# ADC.net
KiCad netlist of a schematic drawn in Altium Designer
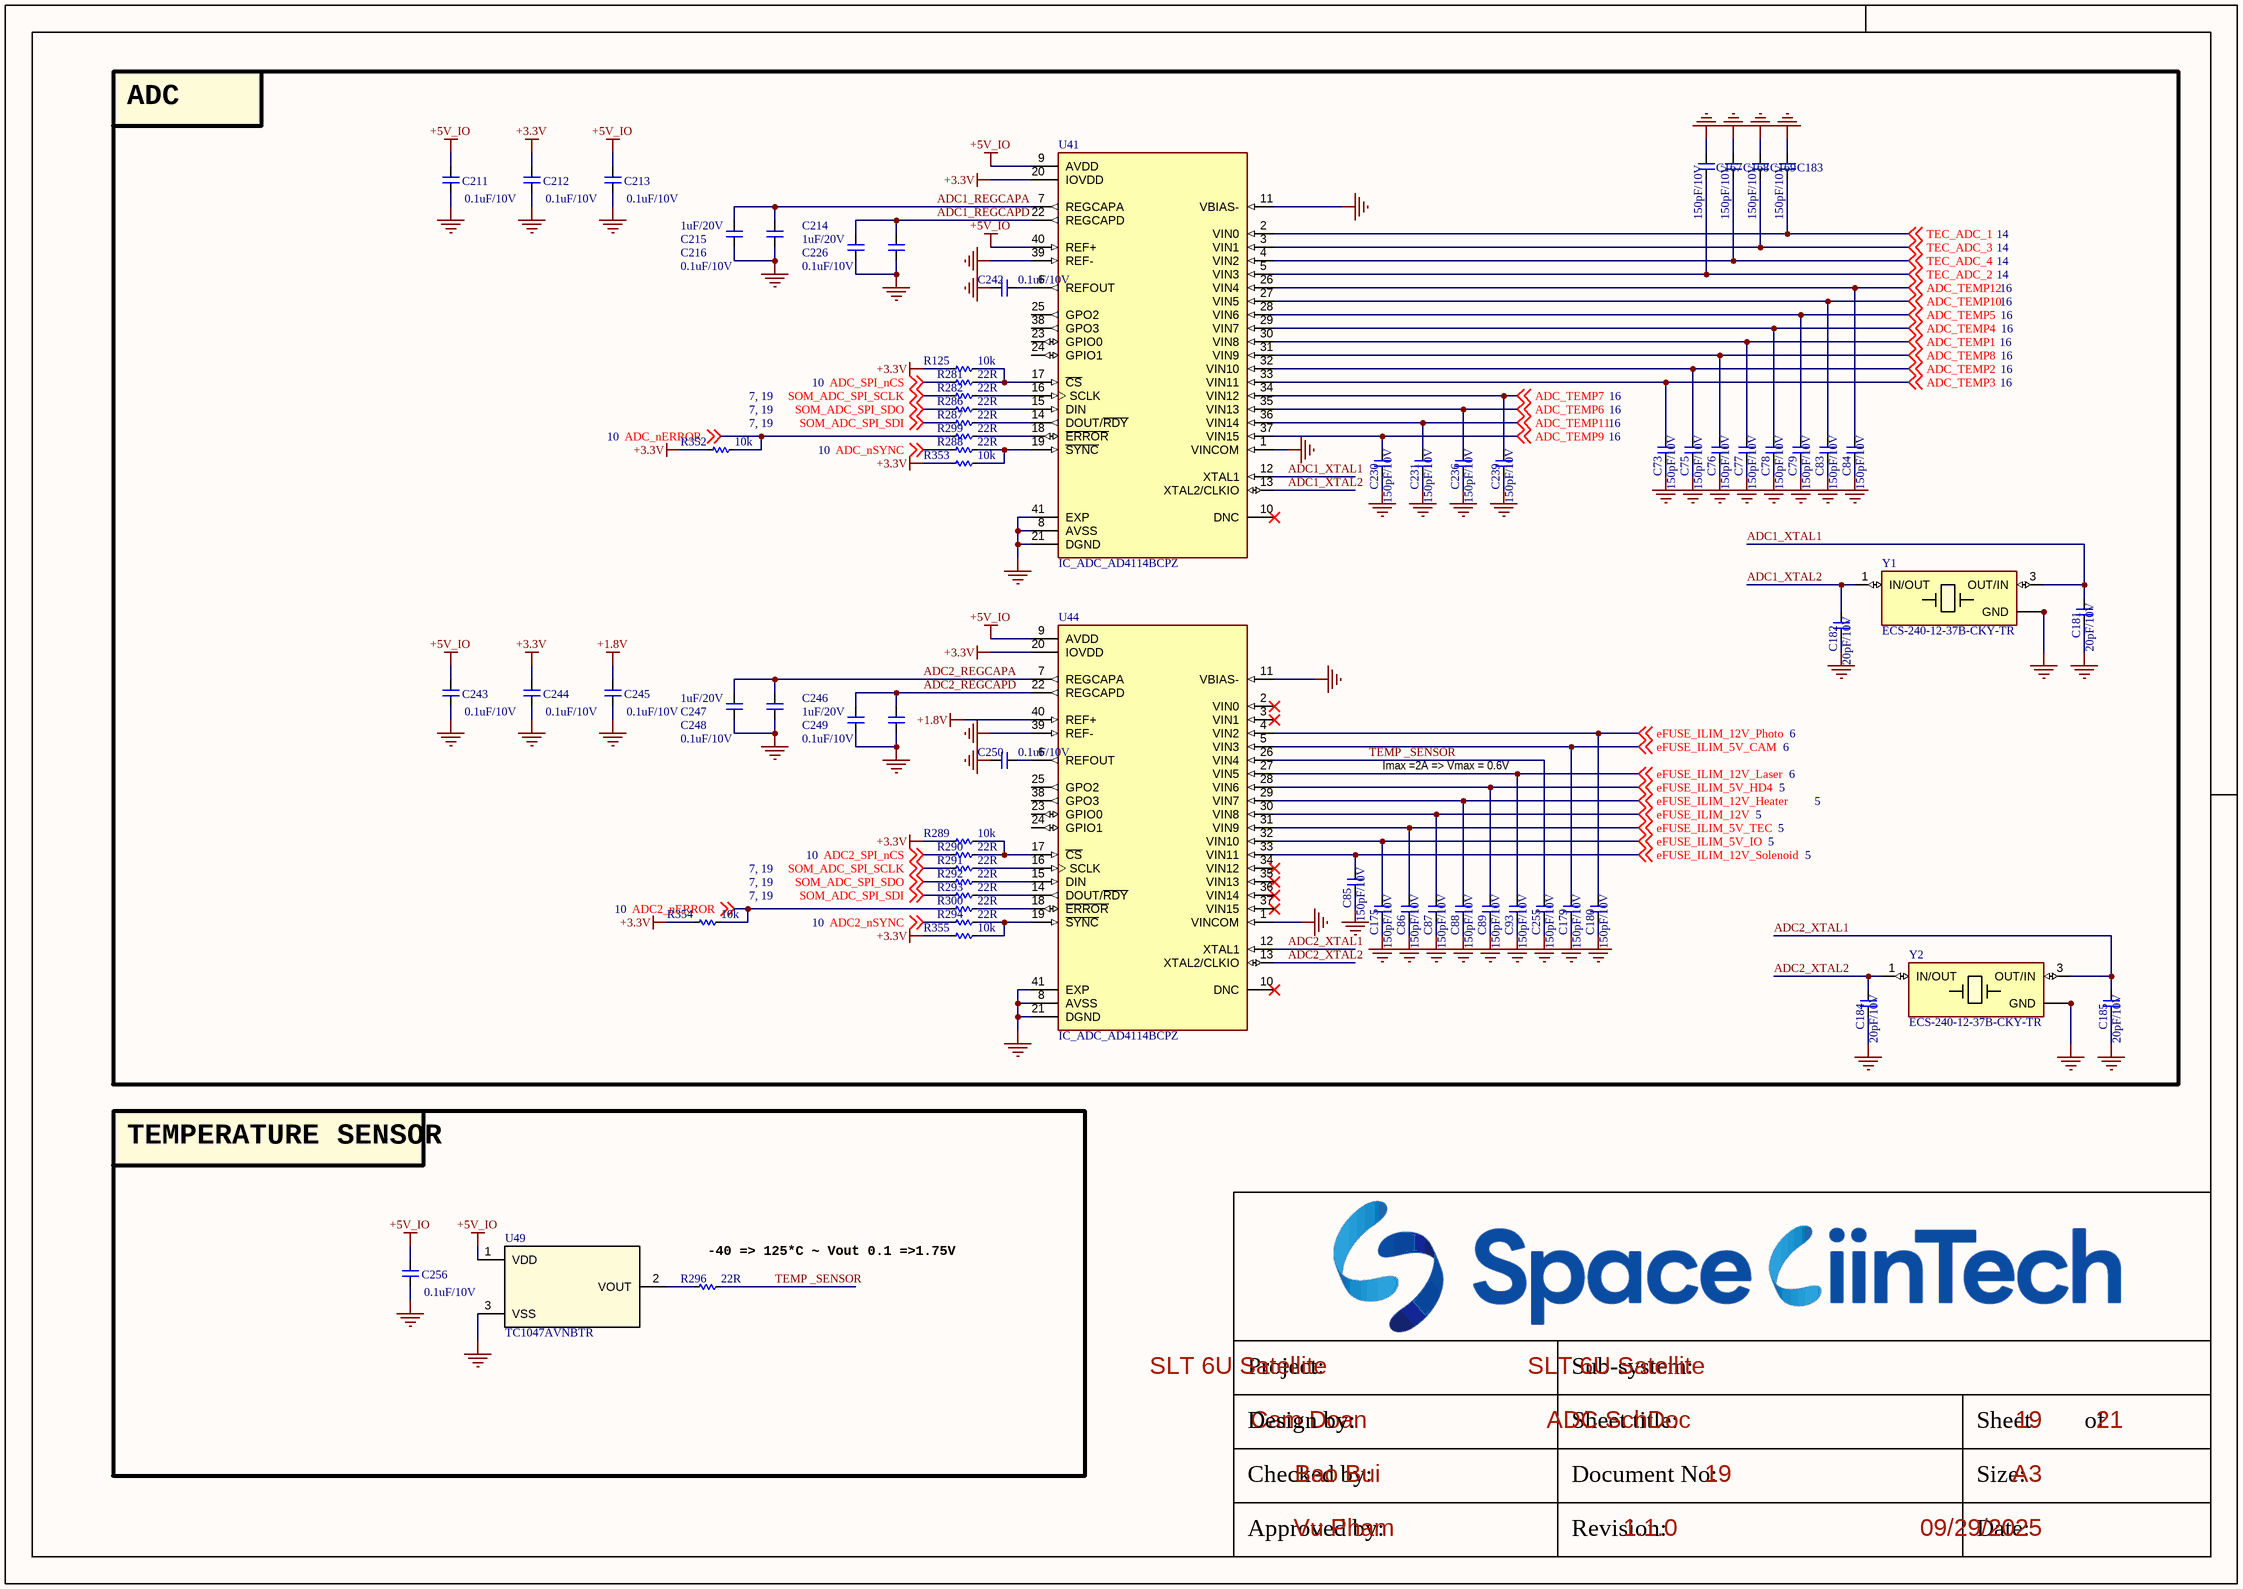
[diagram p0: ADC.SchDoc]

(export (version "E")
  (design (tool "Eeschema 10.0.6"))
  (components
    (comp (ref "C73")
      (value "150pF/10V")
      (footprint "CAP_C_1005X60")
      (description "CAP CHIP")
      (libsource (lib "LABLIB") (part "_CAP_C_2"))
    )
    (comp (ref "C75")
      (value "150pF/10V")
      (footprint "CAP_C_1005X60")
      (description "CAP CHIP")
      (libsource (lib "LABLIB") (part "_CAP_C_2"))
    )
    (comp (ref "C76")
      (value "150pF/10V")
      (footprint "CAP_C_1005X60")
      (description "CAP CHIP")
      (libsource (lib "LABLIB") (part "_CAP_C_2"))
    )
    (comp (ref "C77")
      (value "150pF/10V")
      (footprint "CAP_C_1005X60")
      (description "CAP CHIP")
      (libsource (lib "LABLIB") (part "_CAP_C_2"))
    )
    (comp (ref "C78")
      (value "150pF/10V")
      (footprint "CAP_C_1005X60")
      (description "CAP CHIP")
      (libsource (lib "LABLIB") (part "_CAP_C_2"))
    )
    (comp (ref "C79")
      (value "150pF/10V")
      (footprint "CAP_C_1005X60")
      (description "CAP CHIP")
      (libsource (lib "LABLIB") (part "_CAP_C_2"))
    )
    (comp (ref "C83")
      (value "150pF/10V")
      (footprint "CAP_C_1005X60")
      (description "CAP CHIP")
      (libsource (lib "LABLIB") (part "_CAP_C_2"))
    )
    (comp (ref "C84")
      (value "150pF/10V")
      (footprint "CAP_C_1005X60")
      (description "CAP CHIP")
      (libsource (lib "LABLIB") (part "_CAP_C_2"))
    )
    (comp (ref "C85")
      (value "150pF/10V")
      (footprint "CAP_C_1005X60")
      (description "CAP CHIP")
      (libsource (lib "LABLIB") (part "_CAP_C_2"))
    )
    (comp (ref "C86")
      (value "150pF/10V")
      (footprint "CAP_C_1005X60")
      (description "CAP CHIP")
      (libsource (lib "LABLIB") (part "_CAP_C_2"))
    )
    (comp (ref "C87")
      (value "150pF/10V")
      (footprint "CAP_C_1005X60")
      (description "CAP CHIP")
      (libsource (lib "LABLIB") (part "_CAP_C_2"))
    )
    (comp (ref "C88")
      (value "150pF/10V")
      (footprint "CAP_C_1005X60")
      (description "CAP CHIP")
      (libsource (lib "LABLIB") (part "_CAP_C_2"))
    )
    (comp (ref "C89")
      (value "150pF/10V")
      (footprint "CAP_C_1005X60")
      (description "CAP CHIP")
      (libsource (lib "LABLIB") (part "_CAP_C_2"))
    )
    (comp (ref "C93")
      (value "150pF/10V")
      (footprint "CAP_C_1005X60")
      (description "CAP CHIP")
      (libsource (lib "LABLIB") (part "_CAP_C_2"))
    )
    (comp (ref "C167")
      (value "150pF/10V")
      (footprint "CAP_C_1005X60")
      (description "CAP CHIP")
      (libsource (lib "LABLIB") (part "_CAP_C_2"))
    )
    (comp (ref "C168")
      (value "150pF/10V")
      (footprint "CAP_C_1005X60")
      (description "CAP CHIP")
      (libsource (lib "LABLIB") (part "_CAP_C_2"))
    )
    (comp (ref "C169")
      (value "150pF/10V")
      (footprint "CAP_C_1005X60")
      (description "CAP CHIP")
      (libsource (lib "LABLIB") (part "_CAP_C_2"))
    )
    (comp (ref "C175")
      (value "150pF/10V")
      (footprint "CAP_C_1005X60")
      (description "CAP CHIP")
      (libsource (lib "LABLIB") (part "_CAP_C_2"))
    )
    (comp (ref "C179")
      (value "150pF/10V")
      (footprint "CAP_C_1005X60")
      (description "CAP CHIP")
      (libsource (lib "LABLIB") (part "_CAP_C_2"))
    )
    (comp (ref "C180")
      (value "150pF/10V")
      (footprint "CAP_C_1005X60")
      (description "CAP CHIP")
      (libsource (lib "LABLIB") (part "_CAP_C_2"))
    )
    (comp (ref "C181")
      (value "20pF/10V")
      (footprint "CAP_C_1005X60")
      (description "CAP CHIP")
      (libsource (lib "LABLIB") (part "_CAP_C_2"))
    )
    (comp (ref "C182")
      (value "20pF/10V")
      (footprint "CAP_C_1005X60")
      (description "CAP CHIP")
      (libsource (lib "LABLIB") (part "_CAP_C_2"))
    )
    (comp (ref "C183")
      (value "150pF/10V")
      (footprint "CAP_C_1005X60")
      (description "CAP CHIP")
      (libsource (lib "LABLIB") (part "_CAP_C_2"))
    )
    (comp (ref "C184")
      (value "20pF/10V")
      (footprint "CAP_C_1005X60")
      (description "CAP CHIP")
      (libsource (lib "LABLIB") (part "_CAP_C_2"))
    )
    (comp (ref "C185")
      (value "20pF/10V")
      (footprint "CAP_C_1005X60")
      (description "CAP CHIP")
      (libsource (lib "LABLIB") (part "_CAP_C_2"))
    )
    (comp (ref "C211")
      (value "0.1uF/10V")
      (footprint "CAP_C_1005X60")
      (description "CAP CHIP")
      (libsource (lib "LABLIB") (part "_CAP_C_2"))
    )
    (comp (ref "C212")
      (value "0.1uF/10V")
      (footprint "CAP_C_1005X60")
      (description "CAP CHIP")
      (libsource (lib "LABLIB") (part "_CAP_C_2"))
    )
    (comp (ref "C213")
      (value "0.1uF/10V")
      (footprint "CAP_C_1005X60")
      (description "CAP CHIP")
      (libsource (lib "LABLIB") (part "_CAP_C_2"))
    )
    (comp (ref "C214")
      (value "1uF/20V")
      (footprint "CAP_C_1005X60")
      (description "CAP CHIP")
      (libsource (lib "LABLIB") (part "_CAP_C_2"))
    )
    (comp (ref "C215")
      (value "1uF/20V")
      (footprint "CAP_C_1005X60")
      (description "CAP CHIP")
      (libsource (lib "LABLIB") (part "_CAP_C_2"))
    )
    (comp (ref "C216")
      (value "0.1uF/10V")
      (footprint "CAP_C_1005X60")
      (description "CAP CHIP")
      (libsource (lib "LABLIB") (part "_CAP_C_2"))
    )
    (comp (ref "C226")
      (value "0.1uF/10V")
      (footprint "CAP_C_1005X60")
      (description "CAP CHIP")
      (libsource (lib "LABLIB") (part "_CAP_C_2"))
    )
    (comp (ref "C230")
      (value "150pF/10V")
      (footprint "CAP_C_1005X60")
      (description "CAP CHIP")
      (libsource (lib "LABLIB") (part "_CAP_C_2"))
    )
    (comp (ref "C231")
      (value "150pF/10V")
      (footprint "CAP_C_1005X60")
      (description "CAP CHIP")
      (libsource (lib "LABLIB") (part "_CAP_C_2"))
    )
    (comp (ref "C236")
      (value "150pF/10V")
      (footprint "CAP_C_1005X60")
      (description "CAP CHIP")
      (libsource (lib "LABLIB") (part "_CAP_C_2"))
    )
    (comp (ref "C239")
      (value "150pF/10V")
      (footprint "CAP_C_1005X60")
      (description "CAP CHIP")
      (libsource (lib "LABLIB") (part "_CAP_C_2"))
    )
    (comp (ref "C242")
      (value "0.1uF/10V")
      (footprint "CAP_C_1005X60")
      (description "CAP CHIP")
      (libsource (lib "LABLIB") (part "_CAP_C_2"))
    )
    (comp (ref "C243")
      (value "0.1uF/10V")
      (footprint "CAP_C_1005X60")
      (description "CAP CHIP")
      (libsource (lib "LABLIB") (part "_CAP_C_2"))
    )
    (comp (ref "C244")
      (value "0.1uF/10V")
      (footprint "CAP_C_1005X60")
      (description "CAP CHIP")
      (libsource (lib "LABLIB") (part "_CAP_C_2"))
    )
    (comp (ref "C245")
      (value "0.1uF/10V")
      (footprint "CAP_C_1005X60")
      (description "CAP CHIP")
      (libsource (lib "LABLIB") (part "_CAP_C_2"))
    )
    (comp (ref "C246")
      (value "1uF/20V")
      (footprint "CAP_C_1005X60")
      (description "CAP CHIP")
      (libsource (lib "LABLIB") (part "_CAP_C_2"))
    )
    (comp (ref "C247")
      (value "1uF/20V")
      (footprint "CAP_C_1005X60")
      (description "CAP CHIP")
      (libsource (lib "LABLIB") (part "_CAP_C_2"))
    )
    (comp (ref "C248")
      (value "0.1uF/10V")
      (footprint "CAP_C_1005X60")
      (description "CAP CHIP")
      (libsource (lib "LABLIB") (part "_CAP_C_2"))
    )
    (comp (ref "C249")
      (value "0.1uF/10V")
      (footprint "CAP_C_1005X60")
      (description "CAP CHIP")
      (libsource (lib "LABLIB") (part "_CAP_C_2"))
    )
    (comp (ref "C250")
      (value "0.1uF/10V")
      (footprint "CAP_C_1005X60")
      (description "CAP CHIP")
      (libsource (lib "LABLIB") (part "_CAP_C_2"))
    )
    (comp (ref "C255")
      (value "150pF/10V")
      (footprint "CAP_C_1005X60")
      (description "CAP CHIP")
      (libsource (lib "LABLIB") (part "_CAP_C_2"))
    )
    (comp (ref "C256")
      (value "0.1uF/10V")
      (footprint "CAP_C_1005X60")
      (description "CAP CHIP")
      (libsource (lib "LABLIB") (part "_CAP_C_2"))
    )
    (comp (ref "R125")
      (value "10k")
      (footprint "RES_C_1005X40")
      (description "RES")
      (libsource (lib "LABLIB") (part "_RES_B_2"))
    )
    (comp (ref "R281")
      (value "22R")
      (footprint "RES_C_1005X40")
      (description "RES")
      (libsource (lib "LABLIB") (part "_RES_B_2"))
    )
    (comp (ref "R282")
      (value "22R")
      (footprint "RES_C_1005X40")
      (description "RES")
      (libsource (lib "LABLIB") (part "_RES_B_2"))
    )
    (comp (ref "R286")
      (value "22R")
      (footprint "RES_C_1005X40")
      (description "RES")
      (libsource (lib "LABLIB") (part "_RES_B_2"))
    )
    (comp (ref "R287")
      (value "22R")
      (footprint "RES_C_1005X40")
      (description "RES")
      (libsource (lib "LABLIB") (part "_RES_B_2"))
    )
    (comp (ref "R288")
      (value "22R")
      (footprint "RES_C_1005X40")
      (description "RES")
      (libsource (lib "LABLIB") (part "_RES_B_2"))
    )
    (comp (ref "R289")
      (value "10k")
      (footprint "RES_C_1005X40")
      (description "RES")
      (libsource (lib "LABLIB") (part "_RES_B_2"))
    )
    (comp (ref "R290")
      (value "22R")
      (footprint "RES_C_1005X40")
      (description "RES")
      (libsource (lib "LABLIB") (part "_RES_B_2"))
    )
    (comp (ref "R291")
      (value "22R")
      (footprint "RES_C_1005X40")
      (description "RES")
      (libsource (lib "LABLIB") (part "_RES_B_2"))
    )
    (comp (ref "R292")
      (value "22R")
      (footprint "RES_C_1005X40")
      (description "RES")
      (libsource (lib "LABLIB") (part "_RES_B_2"))
    )
    (comp (ref "R293")
      (value "22R")
      (footprint "RES_C_1005X40")
      (description "RES")
      (libsource (lib "LABLIB") (part "_RES_B_2"))
    )
    (comp (ref "R294")
      (value "22R")
      (footprint "RES_C_1005X40")
      (description "RES")
      (libsource (lib "LABLIB") (part "_RES_B_2"))
    )
    (comp (ref "R296")
      (value "22R")
      (footprint "RES_C_1005X40")
      (description "RES")
      (libsource (lib "LABLIB") (part "_RES_B_2"))
    )
    (comp (ref "R299")
      (value "22R")
      (footprint "RES_C_1005X40")
      (description "RES")
      (libsource (lib "LABLIB") (part "_RES_B_2"))
    )
    (comp (ref "R300")
      (value "22R")
      (footprint "RES_C_1005X40")
      (description "RES")
      (libsource (lib "LABLIB") (part "_RES_B_2"))
    )
    (comp (ref "R352")
      (value "10k")
      (footprint "RES_C_1005X40")
      (description "RES")
      (libsource (lib "LABLIB") (part "_RES_B_2"))
    )
    (comp (ref "R353")
      (value "10k")
      (footprint "RES_C_1005X40")
      (description "RES")
      (libsource (lib "LABLIB") (part "_RES_B_2"))
    )
    (comp (ref "R354")
      (value "10k")
      (footprint "RES_C_1005X40")
      (description "RES")
      (libsource (lib "LABLIB") (part "_RES_B_2"))
    )
    (comp (ref "R355")
      (value "10k")
      (footprint "RES_C_1005X40")
      (description "RES")
      (libsource (lib "LABLIB") (part "_RES_B_2"))
    )
    (comp (ref "U41")
      (value "IC_ADC_AD4114BCPZ")
      (footprint "QFN50P600X600X100-41N")
      (description "Single Supply, Multichannel, 31.25 kSPS, 24-Bit, Sigma-Delta ADC with Â±10 V Inputs")
      (fields (field (name "MP") "AD4114BCPZ") (field (name "MF") "Analog Devices"))
      (libsource (lib "LABLIB") (part "IC_ADC_AD4114BCPZ"))
    )
    (comp (ref "U44")
      (value "IC_ADC_AD4114BCPZ")
      (footprint "QFN50P600X600X100-41N")
      (description "Single Supply, Multichannel, 31.25 kSPS, 24-Bit, Sigma-Delta ADC with Â±10 V Inputs")
      (fields (field (name "MP") "AD4114BCPZ") (field (name "MF") "Analog Devices"))
      (libsource (lib "LABLIB") (part "IC_ADC_AD4114BCPZ"))
    )
    (comp (ref "U49")
      (value "TC1047AVNBTR")
      (footprint "SOT95P240X120-3N")
      (description "Temperature Sensor Analog, Local -40°C ~ 125°C 10mV/°C SOT-23-3")
      (libsource (lib "LABLIB") (part "IC_SENSOR_TC1047AVNBTR"))
    )
    (comp (ref "Y1")
      (value "ECS-240-12-37B-CKY-TR")
      (footprint "XTAL_ECS-240-12-37B-CKY-TR")
      (libsource (lib "ECS-240-12-37B-CKY-TR") (part "ECS-240-12-37B-CKY-TR"))
    )
    (comp (ref "Y2")
      (value "ECS-240-12-37B-CKY-TR")
      (footprint "XTAL_ECS-240-12-37B-CKY-TR")
      (libsource (lib "ECS-240-12-37B-CKY-TR") (part "ECS-240-12-37B-CKY-TR"))
    )
  )
  (nets
    (net (code "1") (name "+1.8V") (class "Default")
      (node (ref "C245") (pin "2") (pinfunction "2_2") (pintype "passive"))
      (node (ref "U44") (pin "40") (pinfunction "REF+_40") (pintype "input"))
    )
    (net (code "2") (name "+3.3V") (class "Default")
      (node (ref "C212") (pin "2") (pinfunction "2_2") (pintype "passive"))
      (node (ref "C244") (pin "2") (pinfunction "2_2") (pintype "passive"))
      (node (ref "R125") (pin "2") (pinfunction "2_2") (pintype "passive"))
      (node (ref "R289") (pin "2") (pinfunction "2_2") (pintype "passive"))
      (node (ref "R352") (pin "2") (pinfunction "2_2") (pintype "passive"))
      (node (ref "R353") (pin "2") (pinfunction "2_2") (pintype "passive"))
      (node (ref "R354") (pin "2") (pinfunction "2_2") (pintype "passive"))
      (node (ref "R355") (pin "2") (pinfunction "2_2") (pintype "passive"))
      (node (ref "U41") (pin "20") (pinfunction "IOVDD_20") (pintype "power_in"))
      (node (ref "U44") (pin "20") (pinfunction "IOVDD_20") (pintype "power_in"))
    )
    (net (code "3") (name "+5V_IO") (class "Default")
      (node (ref "C211") (pin "2") (pinfunction "2_2") (pintype "passive"))
      (node (ref "C213") (pin "2") (pinfunction "2_2") (pintype "passive"))
      (node (ref "C243") (pin "2") (pinfunction "2_2") (pintype "passive"))
      (node (ref "C256") (pin "2") (pinfunction "2_2") (pintype "passive"))
      (node (ref "U41") (pin "40") (pinfunction "REF+_40") (pintype "input"))
      (node (ref "U41") (pin "9") (pinfunction "AVDD_9") (pintype "power_in"))
      (node (ref "U44") (pin "9") (pinfunction "AVDD_9") (pintype "power_in"))
      (node (ref "U49") (pin "1") (pinfunction "VDD_1") (pintype "passive"))
    )
    (net (code "4") (name "/ADC1_REGCAPA") (class "Default")
      (node (ref "C215") (pin "2") (pinfunction "2_2") (pintype "passive"))
      (node (ref "C216") (pin "2") (pinfunction "2_2") (pintype "passive"))
      (node (ref "U41") (pin "7") (pinfunction "REGCAPA_7") (pintype "output"))
    )
    (net (code "5") (name "/ADC1_REGCAPD") (class "Default")
      (node (ref "C214") (pin "2") (pinfunction "2_2") (pintype "passive"))
      (node (ref "C226") (pin "2") (pinfunction "2_2") (pintype "passive"))
      (node (ref "U41") (pin "22") (pinfunction "REGCAPD_22") (pintype "output"))
    )
    (net (code "6") (name "/ADC1_XTAL1") (class "Default")
      (node (ref "C181") (pin "2") (pinfunction "2_2") (pintype "passive"))
      (node (ref "U41") (pin "12") (pinfunction "XTAL1_12") (pintype "input"))
      (node (ref "Y1") (pin "3") (pinfunction "OUT/IN_3") (pintype "bidirectional"))
    )
    (net (code "7") (name "/ADC1_XTAL2") (class "Default")
      (node (ref "C182") (pin "2") (pinfunction "2_2") (pintype "passive"))
      (node (ref "U41") (pin "13") (pinfunction "XTAL2/CLKIO_13") (pintype "bidirectional"))
      (node (ref "Y1") (pin "1") (pinfunction "IN/OUT_1") (pintype "bidirectional"))
    )
    (net (code "8") (name "/ADC2_REGCAPA") (class "Default")
      (node (ref "C247") (pin "2") (pinfunction "2_2") (pintype "passive"))
      (node (ref "C248") (pin "2") (pinfunction "2_2") (pintype "passive"))
      (node (ref "U44") (pin "7") (pinfunction "REGCAPA_7") (pintype "output"))
    )
    (net (code "9") (name "/ADC2_REGCAPD") (class "Default")
      (node (ref "C246") (pin "2") (pinfunction "2_2") (pintype "passive"))
      (node (ref "C249") (pin "2") (pinfunction "2_2") (pintype "passive"))
      (node (ref "U44") (pin "22") (pinfunction "REGCAPD_22") (pintype "output"))
    )
    (net (code "10") (name "/ADC2_XTAL1") (class "Default")
      (node (ref "C185") (pin "2") (pinfunction "2_2") (pintype "passive"))
      (node (ref "U44") (pin "12") (pinfunction "XTAL1_12") (pintype "input"))
      (node (ref "Y2") (pin "3") (pinfunction "OUT/IN_3") (pintype "bidirectional"))
    )
    (net (code "11") (name "/ADC2_XTAL2") (class "Default")
      (node (ref "C184") (pin "2") (pinfunction "2_2") (pintype "passive"))
      (node (ref "U44") (pin "13") (pinfunction "XTAL2/CLKIO_13") (pintype "bidirectional"))
      (node (ref "Y2") (pin "1") (pinfunction "IN/OUT_1") (pintype "bidirectional"))
    )
    (net (code "12") (name "/TEMP _SENSOR") (class "Default")
      (node (ref "C255") (pin "2") (pinfunction "2_2") (pintype "passive"))
      (node (ref "R296") (pin "2") (pinfunction "2_2") (pintype "passive"))
      (node (ref "U44") (pin "26") (pinfunction "VIN4_26") (pintype "input"))
    )
    (net (code "13") (name "ADC2_SPI_nCS") (class "Default")
      (node (ref "R290") (pin "1") (pinfunction "1_1") (pintype "passive"))
    )
    (net (code "14") (name "ADC2_nERROR") (class "Default")
      (node (ref "R300") (pin "1") (pinfunction "1_1") (pintype "passive"))
      (node (ref "R354") (pin "1") (pinfunction "1_1") (pintype "passive"))
    )
    (net (code "15") (name "ADC2_nSYNC") (class "Default")
      (node (ref "R294") (pin "1") (pinfunction "1_1") (pintype "passive"))
    )
    (net (code "16") (name "ADC_SPI_nCS") (class "Default")
      (node (ref "R281") (pin "1") (pinfunction "1_1") (pintype "passive"))
    )
    (net (code "17") (name "ADC_TEMP1") (class "Default")
      (node (ref "C77") (pin "2") (pinfunction "2_2") (pintype "passive"))
      (node (ref "U41") (pin "30") (pinfunction "VIN8_30") (pintype "input"))
    )
    (net (code "18") (name "ADC_TEMP2") (class "Default")
      (node (ref "C75") (pin "2") (pinfunction "2_2") (pintype "passive"))
      (node (ref "U41") (pin "32") (pinfunction "VIN10_32") (pintype "input"))
    )
    (net (code "19") (name "ADC_TEMP3") (class "Default")
      (node (ref "C73") (pin "2") (pinfunction "2_2") (pintype "passive"))
      (node (ref "U41") (pin "33") (pinfunction "VIN11_33") (pintype "input"))
    )
    (net (code "20") (name "ADC_TEMP4") (class "Default")
      (node (ref "C78") (pin "2") (pinfunction "2_2") (pintype "passive"))
      (node (ref "U41") (pin "29") (pinfunction "VIN7_29") (pintype "input"))
    )
    (net (code "21") (name "ADC_TEMP5") (class "Default")
      (node (ref "C79") (pin "2") (pinfunction "2_2") (pintype "passive"))
      (node (ref "U41") (pin "28") (pinfunction "VIN6_28") (pintype "input"))
    )
    (net (code "22") (name "ADC_TEMP6") (class "Default")
      (node (ref "C236") (pin "2") (pinfunction "2_2") (pintype "passive"))
      (node (ref "U41") (pin "35") (pinfunction "VIN13_35") (pintype "input"))
    )
    (net (code "23") (name "ADC_TEMP7") (class "Default")
      (node (ref "C239") (pin "2") (pinfunction "2_2") (pintype "passive"))
      (node (ref "U41") (pin "34") (pinfunction "VIN12_34") (pintype "input"))
    )
    (net (code "24") (name "ADC_TEMP8") (class "Default")
      (node (ref "C76") (pin "2") (pinfunction "2_2") (pintype "passive"))
      (node (ref "U41") (pin "31") (pinfunction "VIN9_31") (pintype "input"))
    )
    (net (code "25") (name "ADC_TEMP9") (class "Default")
      (node (ref "C230") (pin "2") (pinfunction "2_2") (pintype "passive"))
      (node (ref "U41") (pin "37") (pinfunction "VIN15_37") (pintype "input"))
    )
    (net (code "26") (name "ADC_TEMP10") (class "Default")
      (node (ref "C83") (pin "2") (pinfunction "2_2") (pintype "passive"))
      (node (ref "U41") (pin "27") (pinfunction "VIN5_27") (pintype "input"))
    )
    (net (code "27") (name "ADC_TEMP11") (class "Default")
      (node (ref "C231") (pin "2") (pinfunction "2_2") (pintype "passive"))
      (node (ref "U41") (pin "36") (pinfunction "VIN14_36") (pintype "input"))
    )
    (net (code "28") (name "ADC_TEMP12") (class "Default")
      (node (ref "C84") (pin "2") (pinfunction "2_2") (pintype "passive"))
      (node (ref "U41") (pin "26") (pinfunction "VIN4_26") (pintype "input"))
    )
    (net (code "29") (name "ADC_nERROR") (class "Default")
      (node (ref "R299") (pin "1") (pinfunction "1_1") (pintype "passive"))
      (node (ref "R352") (pin "1") (pinfunction "1_1") (pintype "passive"))
    )
    (net (code "30") (name "ADC_nSYNC") (class "Default")
      (node (ref "R288") (pin "1") (pinfunction "1_1") (pintype "passive"))
    )
    (net (code "31") (name "GND") (class "Default")
      (node (ref "C167") (pin "1") (pinfunction "1_1") (pintype "passive"))
      (node (ref "C168") (pin "1") (pinfunction "1_1") (pintype "passive"))
      (node (ref "C169") (pin "1") (pinfunction "1_1") (pintype "passive"))
      (node (ref "C175") (pin "1") (pinfunction "1_1") (pintype "passive"))
      (node (ref "C179") (pin "1") (pinfunction "1_1") (pintype "passive"))
      (node (ref "C180") (pin "1") (pinfunction "1_1") (pintype "passive"))
      (node (ref "C181") (pin "1") (pinfunction "1_1") (pintype "passive"))
      (node (ref "C182") (pin "1") (pinfunction "1_1") (pintype "passive"))
      (node (ref "C183") (pin "1") (pinfunction "1_1") (pintype "passive"))
      (node (ref "C184") (pin "1") (pinfunction "1_1") (pintype "passive"))
      (node (ref "C185") (pin "1") (pinfunction "1_1") (pintype "passive"))
      (node (ref "C211") (pin "1") (pinfunction "1_1") (pintype "passive"))
      (node (ref "C212") (pin "1") (pinfunction "1_1") (pintype "passive"))
      (node (ref "C213") (pin "1") (pinfunction "1_1") (pintype "passive"))
      (node (ref "C214") (pin "1") (pinfunction "1_1") (pintype "passive"))
      (node (ref "C215") (pin "1") (pinfunction "1_1") (pintype "passive"))
      (node (ref "C216") (pin "1") (pinfunction "1_1") (pintype "passive"))
      (node (ref "C226") (pin "1") (pinfunction "1_1") (pintype "passive"))
      (node (ref "C230") (pin "1") (pinfunction "1_1") (pintype "passive"))
      (node (ref "C231") (pin "1") (pinfunction "1_1") (pintype "passive"))
      (node (ref "C236") (pin "1") (pinfunction "1_1") (pintype "passive"))
      (node (ref "C239") (pin "1") (pinfunction "1_1") (pintype "passive"))
      (node (ref "C242") (pin "1") (pinfunction "1_1") (pintype "passive"))
      (node (ref "C243") (pin "1") (pinfunction "1_1") (pintype "passive"))
      (node (ref "C244") (pin "1") (pinfunction "1_1") (pintype "passive"))
      (node (ref "C245") (pin "1") (pinfunction "1_1") (pintype "passive"))
      (node (ref "C246") (pin "1") (pinfunction "1_1") (pintype "passive"))
      (node (ref "C247") (pin "1") (pinfunction "1_1") (pintype "passive"))
      (node (ref "C248") (pin "1") (pinfunction "1_1") (pintype "passive"))
      (node (ref "C249") (pin "1") (pinfunction "1_1") (pintype "passive"))
      (node (ref "C250") (pin "1") (pinfunction "1_1") (pintype "passive"))
      (node (ref "C255") (pin "1") (pinfunction "1_1") (pintype "passive"))
      (node (ref "C256") (pin "1") (pinfunction "1_1") (pintype "passive"))
      (node (ref "C73") (pin "1") (pinfunction "1_1") (pintype "passive"))
      (node (ref "C75") (pin "1") (pinfunction "1_1") (pintype "passive"))
      (node (ref "C76") (pin "1") (pinfunction "1_1") (pintype "passive"))
      (node (ref "C77") (pin "1") (pinfunction "1_1") (pintype "passive"))
      (node (ref "C78") (pin "1") (pinfunction "1_1") (pintype "passive"))
      (node (ref "C79") (pin "1") (pinfunction "1_1") (pintype "passive"))
      (node (ref "C83") (pin "1") (pinfunction "1_1") (pintype "passive"))
      (node (ref "C84") (pin "1") (pinfunction "1_1") (pintype "passive"))
      (node (ref "C85") (pin "1") (pinfunction "1_1") (pintype "passive"))
      (node (ref "C86") (pin "1") (pinfunction "1_1") (pintype "passive"))
      (node (ref "C87") (pin "1") (pinfunction "1_1") (pintype "passive"))
      (node (ref "C88") (pin "1") (pinfunction "1_1") (pintype "passive"))
      (node (ref "C89") (pin "1") (pinfunction "1_1") (pintype "passive"))
      (node (ref "C93") (pin "1") (pinfunction "1_1") (pintype "passive"))
      (node (ref "U41") (pin "1") (pinfunction "VINCOM_1") (pintype "input"))
      (node (ref "U41") (pin "11") (pinfunction "VBIAS-_11") (pintype "input"))
      (node (ref "U41") (pin "21") (pinfunction "DGND_21") (pintype "power_in"))
      (node (ref "U41") (pin "39") (pinfunction "REF-_39") (pintype "input"))
      (node (ref "U41") (pin "41") (pinfunction "EXP_41") (pintype "power_in"))
      (node (ref "U41") (pin "8") (pinfunction "AVSS_8") (pintype "power_in"))
      (node (ref "U44") (pin "1") (pinfunction "VINCOM_1") (pintype "input"))
      (node (ref "U44") (pin "11") (pinfunction "VBIAS-_11") (pintype "input"))
      (node (ref "U44") (pin "21") (pinfunction "DGND_21") (pintype "power_in"))
      (node (ref "U44") (pin "39") (pinfunction "REF-_39") (pintype "input"))
      (node (ref "U44") (pin "41") (pinfunction "EXP_41") (pintype "power_in"))
      (node (ref "U44") (pin "8") (pinfunction "AVSS_8") (pintype "power_in"))
      (node (ref "U49") (pin "3") (pinfunction "VSS_3") (pintype "passive"))
      (node (ref "Y1") (pin "2") (pinfunction "GND_2") (pintype "power_in"))
      (node (ref "Y1") (pin "4") (pinfunction "GND_4") (pintype "power_in"))
      (node (ref "Y2") (pin "2") (pinfunction "GND_2") (pintype "power_in"))
      (node (ref "Y2") (pin "4") (pinfunction "GND_4") (pintype "power_in"))
    )
    (net (code "32") (name "Net-(U41-DIN)") (class "Default")
      (node (ref "R286") (pin "2") (pinfunction "2_2") (pintype "passive"))
      (node (ref "U41") (pin "15") (pinfunction "DIN_15") (pintype "input"))
    )
    (net (code "33") (name "Net-(U41-DOUT{slash}~{RDY})") (class "Default")
      (node (ref "R287") (pin "2") (pinfunction "2_2") (pintype "passive"))
      (node (ref "U41") (pin "14") (pinfunction "DOUT/~{RDY}_14") (pintype "output"))
    )
    (net (code "34") (name "Net-(U41-REFOUT)") (class "Default")
      (node (ref "C242") (pin "2") (pinfunction "2_2") (pintype "passive"))
      (node (ref "U41") (pin "6") (pinfunction "REFOUT_6") (pintype "output"))
    )
    (net (code "35") (name "Net-(U41-SCLK)") (class "Default")
      (node (ref "R282") (pin "2") (pinfunction "2_2") (pintype "passive"))
      (node (ref "U41") (pin "16") (pinfunction "SCLK_16") (pintype "input"))
    )
    (net (code "36") (name "Net-(U41-~{CS})") (class "Default")
      (node (ref "R125") (pin "1") (pinfunction "1_1") (pintype "passive"))
      (node (ref "R281") (pin "2") (pinfunction "2_2") (pintype "passive"))
      (node (ref "U41") (pin "17") (pinfunction "~{CS}_17") (pintype "input"))
    )
    (net (code "37") (name "Net-(U41-~{ERROR})") (class "Default")
      (node (ref "R299") (pin "2") (pinfunction "2_2") (pintype "passive"))
      (node (ref "U41") (pin "18") (pinfunction "~{ERROR}_18") (pintype "bidirectional"))
    )
    (net (code "38") (name "Net-(U41-~{SYNC})") (class "Default")
      (node (ref "R288") (pin "2") (pinfunction "2_2") (pintype "passive"))
      (node (ref "R353") (pin "1") (pinfunction "1_1") (pintype "passive"))
      (node (ref "U41") (pin "19") (pinfunction "~{SYNC}_19") (pintype "input"))
    )
    (net (code "39") (name "Net-(U44-DIN)") (class "Default")
      (node (ref "R292") (pin "2") (pinfunction "2_2") (pintype "passive"))
      (node (ref "U44") (pin "15") (pinfunction "DIN_15") (pintype "input"))
    )
    (net (code "40") (name "Net-(U44-DOUT{slash}~{RDY})") (class "Default")
      (node (ref "R293") (pin "2") (pinfunction "2_2") (pintype "passive"))
      (node (ref "U44") (pin "14") (pinfunction "DOUT/~{RDY}_14") (pintype "output"))
    )
    (net (code "41") (name "Net-(U44-REFOUT)") (class "Default")
      (node (ref "C250") (pin "2") (pinfunction "2_2") (pintype "passive"))
      (node (ref "U44") (pin "6") (pinfunction "REFOUT_6") (pintype "output"))
    )
    (net (code "42") (name "Net-(U44-SCLK)") (class "Default")
      (node (ref "R291") (pin "2") (pinfunction "2_2") (pintype "passive"))
      (node (ref "U44") (pin "16") (pinfunction "SCLK_16") (pintype "input"))
    )
    (net (code "43") (name "Net-(U44-~{CS})") (class "Default")
      (node (ref "R289") (pin "1") (pinfunction "1_1") (pintype "passive"))
      (node (ref "R290") (pin "2") (pinfunction "2_2") (pintype "passive"))
      (node (ref "U44") (pin "17") (pinfunction "~{CS}_17") (pintype "input"))
    )
    (net (code "44") (name "Net-(U44-~{ERROR})") (class "Default")
      (node (ref "R300") (pin "2") (pinfunction "2_2") (pintype "passive"))
      (node (ref "U44") (pin "18") (pinfunction "~{ERROR}_18") (pintype "bidirectional"))
    )
    (net (code "45") (name "Net-(U44-~{SYNC})") (class "Default")
      (node (ref "R294") (pin "2") (pinfunction "2_2") (pintype "passive"))
      (node (ref "R355") (pin "1") (pinfunction "1_1") (pintype "passive"))
      (node (ref "U44") (pin "19") (pinfunction "~{SYNC}_19") (pintype "input"))
    )
    (net (code "46") (name "Net-(U49-VOUT)") (class "Default")
      (node (ref "R296") (pin "1") (pinfunction "1_1") (pintype "passive"))
      (node (ref "U49") (pin "2") (pinfunction "VOUT_2") (pintype "passive"))
    )
    (net (code "47") (name "SOM_ADC_SPI_SCLK") (class "Default")
      (node (ref "R282") (pin "1") (pinfunction "1_1") (pintype "passive"))
      (node (ref "R291") (pin "1") (pinfunction "1_1") (pintype "passive"))
    )
    (net (code "48") (name "SOM_ADC_SPI_SDI") (class "Default")
      (node (ref "R287") (pin "1") (pinfunction "1_1") (pintype "passive"))
      (node (ref "R293") (pin "1") (pinfunction "1_1") (pintype "passive"))
    )
    (net (code "49") (name "SOM_ADC_SPI_SDO") (class "Default")
      (node (ref "R286") (pin "1") (pinfunction "1_1") (pintype "passive"))
      (node (ref "R292") (pin "1") (pinfunction "1_1") (pintype "passive"))
    )
    (net (code "50") (name "TEC_ADC_1") (class "Default")
      (node (ref "C183") (pin "2") (pinfunction "2_2") (pintype "passive"))
      (node (ref "U41") (pin "2") (pinfunction "VIN0_2") (pintype "input"))
    )
    (net (code "51") (name "TEC_ADC_2") (class "Default")
      (node (ref "C167") (pin "2") (pinfunction "2_2") (pintype "passive"))
      (node (ref "U41") (pin "5") (pinfunction "VIN3_5") (pintype "input"))
    )
    (net (code "52") (name "TEC_ADC_3") (class "Default")
      (node (ref "C169") (pin "2") (pinfunction "2_2") (pintype "passive"))
      (node (ref "U41") (pin "3") (pinfunction "VIN1_3") (pintype "input"))
    )
    (net (code "53") (name "TEC_ADC_4") (class "Default")
      (node (ref "C168") (pin "2") (pinfunction "2_2") (pintype "passive"))
      (node (ref "U41") (pin "4") (pinfunction "VIN2_4") (pintype "input"))
    )
    (net (code "54") (name "eFUSE_ILIM_5V_CAM") (class "Default")
      (node (ref "C179") (pin "2") (pinfunction "2_2") (pintype "passive"))
      (node (ref "U44") (pin "5") (pinfunction "VIN3_5") (pintype "input"))
    )
    (net (code "55") (name "eFUSE_ILIM_5V_HD4") (class "Default")
      (node (ref "C89") (pin "2") (pinfunction "2_2") (pintype "passive"))
      (node (ref "U44") (pin "28") (pinfunction "VIN6_28") (pintype "input"))
    )
    (net (code "56") (name "eFUSE_ILIM_5V_IO") (class "Default")
      (node (ref "C175") (pin "2") (pinfunction "2_2") (pintype "passive"))
      (node (ref "U44") (pin "32") (pinfunction "VIN10_32") (pintype "input"))
    )
    (net (code "57") (name "eFUSE_ILIM_5V_TEC") (class "Default")
      (node (ref "C86") (pin "2") (pinfunction "2_2") (pintype "passive"))
      (node (ref "U44") (pin "31") (pinfunction "VIN9_31") (pintype "input"))
    )
    (net (code "58") (name "eFUSE_ILIM_12V") (class "Default")
      (node (ref "C87") (pin "2") (pinfunction "2_2") (pintype "passive"))
      (node (ref "U44") (pin "30") (pinfunction "VIN8_30") (pintype "input"))
    )
    (net (code "59") (name "eFUSE_ILIM_12V_Heater") (class "Default")
      (node (ref "C88") (pin "2") (pinfunction "2_2") (pintype "passive"))
      (node (ref "U44") (pin "29") (pinfunction "VIN7_29") (pintype "input"))
    )
    (net (code "60") (name "eFUSE_ILIM_12V_Laser") (class "Default")
      (node (ref "C93") (pin "2") (pinfunction "2_2") (pintype "passive"))
      (node (ref "U44") (pin "27") (pinfunction "VIN5_27") (pintype "input"))
    )
    (net (code "61") (name "eFUSE_ILIM_12V_Photo") (class "Default")
      (node (ref "C180") (pin "2") (pinfunction "2_2") (pintype "passive"))
      (node (ref "U44") (pin "4") (pinfunction "VIN2_4") (pintype "input"))
    )
    (net (code "62") (name "eFUSE_ILIM_12V_Solenoid") (class "Default")
      (node (ref "C85") (pin "2") (pinfunction "2_2") (pintype "passive"))
      (node (ref "U44") (pin "33") (pinfunction "VIN11_33") (pintype "input"))
    )
    (net (code "63") (name "unconnected-(U41-DNC-Pad10)") (class "Default")
      (node (ref "U41") (pin "10") (pinfunction "DNC_10") (pintype "passive+no_connect"))
    )
    (net (code "64") (name "unconnected-(U41-GPIO0-Pad23)") (class "Default")
      (node (ref "U41") (pin "23") (pinfunction "GPIO0_23") (pintype "bidirectional"))
    )
    (net (code "65") (name "unconnected-(U41-GPIO1-Pad24)") (class "Default")
      (node (ref "U41") (pin "24") (pinfunction "GPIO1_24") (pintype "bidirectional"))
    )
    (net (code "66") (name "unconnected-(U41-GPO2-Pad25)") (class "Default")
      (node (ref "U41") (pin "25") (pinfunction "GPO2_25") (pintype "output"))
    )
    (net (code "67") (name "unconnected-(U41-GPO3-Pad38)") (class "Default")
      (node (ref "U41") (pin "38") (pinfunction "GPO3_38") (pintype "output"))
    )
    (net (code "68") (name "unconnected-(U44-DNC-Pad10)") (class "Default")
      (node (ref "U44") (pin "10") (pinfunction "DNC_10") (pintype "passive+no_connect"))
    )
    (net (code "69") (name "unconnected-(U44-GPIO0-Pad23)") (class "Default")
      (node (ref "U44") (pin "23") (pinfunction "GPIO0_23") (pintype "bidirectional"))
    )
    (net (code "70") (name "unconnected-(U44-GPIO1-Pad24)") (class "Default")
      (node (ref "U44") (pin "24") (pinfunction "GPIO1_24") (pintype "bidirectional"))
    )
    (net (code "71") (name "unconnected-(U44-GPO2-Pad25)") (class "Default")
      (node (ref "U44") (pin "25") (pinfunction "GPO2_25") (pintype "output"))
    )
    (net (code "72") (name "unconnected-(U44-GPO3-Pad38)") (class "Default")
      (node (ref "U44") (pin "38") (pinfunction "GPO3_38") (pintype "output"))
    )
    (net (code "73") (name "unconnected-(U44-VIN0-Pad2)") (class "Default")
      (node (ref "U44") (pin "2") (pinfunction "VIN0_2") (pintype "input+no_connect"))
    )
    (net (code "74") (name "unconnected-(U44-VIN1-Pad3)") (class "Default")
      (node (ref "U44") (pin "3") (pinfunction "VIN1_3") (pintype "input+no_connect"))
    )
    (net (code "75") (name "unconnected-(U44-VIN12-Pad34)") (class "Default")
      (node (ref "U44") (pin "34") (pinfunction "VIN12_34") (pintype "input+no_connect"))
    )
    (net (code "76") (name "unconnected-(U44-VIN13-Pad35)") (class "Default")
      (node (ref "U44") (pin "35") (pinfunction "VIN13_35") (pintype "input+no_connect"))
    )
    (net (code "77") (name "unconnected-(U44-VIN14-Pad36)") (class "Default")
      (node (ref "U44") (pin "36") (pinfunction "VIN14_36") (pintype "input+no_connect"))
    )
    (net (code "78") (name "unconnected-(U44-VIN15-Pad37)") (class "Default")
      (node (ref "U44") (pin "37") (pinfunction "VIN15_37") (pintype "input+no_connect"))
    )
  )
)
